# SLT3-PAY-1Q2T_P4.net
KiCad netlist of a schematic drawn in Altium Designer
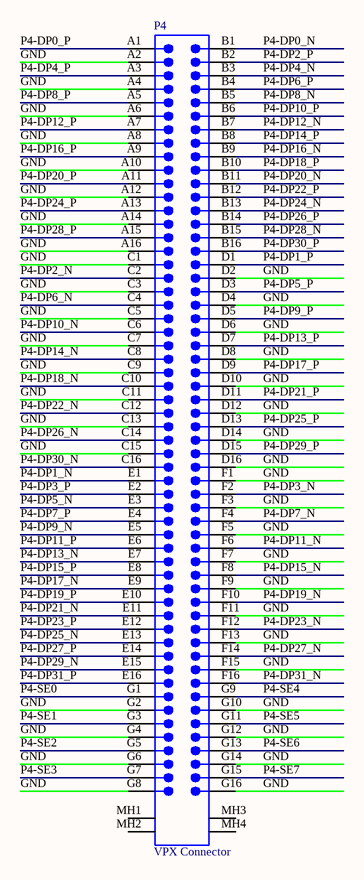
[diagram p0: SLT3-PAY-1Q2T_P4.SchDoc]

(export (version "E")
  (design (tool "Eeschema 10.0.6"))
  (components
    (comp (ref "P4")
      (value "VPX Connector")
      (footprint "BTB1-8-4H112M")
      (description "Ruggedized Board-to-Board Connector, Right Angle, 7-Row, Pitch 1.8mm, 112-Position")
      (fields (field (name "MANUFACTURER") "TE") (field (name "MANUFACTURER PART NUMBER") "2102771-1"))
      (libsource (lib "SVPX") (part "2102771-1"))
    )
  )
  (nets
    (net (code "1") (name "/GND") (class "Default")
      (node (ref "P4") (pin "A10") (pinfunction "A10_A10") (pintype "passive"))
      (node (ref "P4") (pin "A12") (pinfunction "A12_A12") (pintype "passive"))
      (node (ref "P4") (pin "A14") (pinfunction "A14_A14") (pintype "passive"))
      (node (ref "P4") (pin "A16") (pinfunction "A16_A16") (pintype "passive"))
      (node (ref "P4") (pin "A2") (pinfunction "A2_A2") (pintype "passive"))
      (node (ref "P4") (pin "A4") (pinfunction "A4_A4") (pintype "passive"))
      (node (ref "P4") (pin "A6") (pinfunction "A6_A6") (pintype "passive"))
      (node (ref "P4") (pin "A8") (pinfunction "A8_A8") (pintype "passive"))
      (node (ref "P4") (pin "C1") (pinfunction "C1_C1") (pintype "passive"))
      (node (ref "P4") (pin "C11") (pinfunction "C11_C11") (pintype "passive"))
      (node (ref "P4") (pin "C13") (pinfunction "C13_C13") (pintype "passive"))
      (node (ref "P4") (pin "C15") (pinfunction "C15_C15") (pintype "passive"))
      (node (ref "P4") (pin "C3") (pinfunction "C3_C3") (pintype "passive"))
      (node (ref "P4") (pin "C5") (pinfunction "C5_C5") (pintype "passive"))
      (node (ref "P4") (pin "C7") (pinfunction "C7_C7") (pintype "passive"))
      (node (ref "P4") (pin "C9") (pinfunction "C9_C9") (pintype "passive"))
      (node (ref "P4") (pin "D10") (pinfunction "D10_D10") (pintype "passive"))
      (node (ref "P4") (pin "D12") (pinfunction "D12_D12") (pintype "passive"))
      (node (ref "P4") (pin "D14") (pinfunction "D14_D14") (pintype "passive"))
      (node (ref "P4") (pin "D16") (pinfunction "D16_D16") (pintype "passive"))
      (node (ref "P4") (pin "D2") (pinfunction "D2_D2") (pintype "passive"))
      (node (ref "P4") (pin "D4") (pinfunction "D4_D4") (pintype "passive"))
      (node (ref "P4") (pin "D6") (pinfunction "D6_D6") (pintype "passive"))
      (node (ref "P4") (pin "D8") (pinfunction "D8_D8") (pintype "passive"))
      (node (ref "P4") (pin "F1") (pinfunction "F1_F1") (pintype "passive"))
      (node (ref "P4") (pin "F11") (pinfunction "F11_F11") (pintype "passive"))
      (node (ref "P4") (pin "F13") (pinfunction "F13_F13") (pintype "passive"))
      (node (ref "P4") (pin "F15") (pinfunction "F15_F15") (pintype "passive"))
      (node (ref "P4") (pin "F3") (pinfunction "F3_F3") (pintype "passive"))
      (node (ref "P4") (pin "F5") (pinfunction "F5_F5") (pintype "passive"))
      (node (ref "P4") (pin "F7") (pinfunction "F7_F7") (pintype "passive"))
      (node (ref "P4") (pin "F9") (pinfunction "F9_F9") (pintype "passive"))
      (node (ref "P4") (pin "G10") (pinfunction "G10_G10") (pintype "passive"))
      (node (ref "P4") (pin "G12") (pinfunction "G12_G12") (pintype "passive"))
      (node (ref "P4") (pin "G14") (pinfunction "G14_G14") (pintype "passive"))
      (node (ref "P4") (pin "G16") (pinfunction "G16_G16") (pintype "passive"))
      (node (ref "P4") (pin "G2") (pinfunction "G2_G2") (pintype "passive"))
      (node (ref "P4") (pin "G4") (pinfunction "G4_G4") (pintype "passive"))
      (node (ref "P4") (pin "G6") (pinfunction "G6_G6") (pintype "passive"))
      (node (ref "P4") (pin "G8") (pinfunction "G8_G8") (pintype "passive"))
    )
    (net (code "2") (name "/P4-DP0_N") (class "Default")
      (node (ref "P4") (pin "B1") (pinfunction "B1_B1") (pintype "passive"))
    )
    (net (code "3") (name "/P4-DP0_P") (class "Default")
      (node (ref "P4") (pin "A1") (pinfunction "A1_A1") (pintype "passive"))
    )
    (net (code "4") (name "/P4-DP1_N") (class "Default")
      (node (ref "P4") (pin "E1") (pinfunction "E1_E1") (pintype "passive"))
    )
    (net (code "5") (name "/P4-DP1_P") (class "Default")
      (node (ref "P4") (pin "D1") (pinfunction "D1_D1") (pintype "passive"))
    )
    (net (code "6") (name "/P4-DP2_N") (class "Default")
      (node (ref "P4") (pin "C2") (pinfunction "C2_C2") (pintype "passive"))
    )
    (net (code "7") (name "/P4-DP2_P") (class "Default")
      (node (ref "P4") (pin "B2") (pinfunction "B2_B2") (pintype "passive"))
    )
    (net (code "8") (name "/P4-DP3_N") (class "Default")
      (node (ref "P4") (pin "F2") (pinfunction "F2_F2") (pintype "passive"))
    )
    (net (code "9") (name "/P4-DP3_P") (class "Default")
      (node (ref "P4") (pin "E2") (pinfunction "E2_E2") (pintype "passive"))
    )
    (net (code "10") (name "/P4-DP4_N") (class "Default")
      (node (ref "P4") (pin "B3") (pinfunction "B3_B3") (pintype "passive"))
    )
    (net (code "11") (name "/P4-DP4_P") (class "Default")
      (node (ref "P4") (pin "A3") (pinfunction "A3_A3") (pintype "passive"))
    )
    (net (code "12") (name "/P4-DP5_N") (class "Default")
      (node (ref "P4") (pin "E3") (pinfunction "E3_E3") (pintype "passive"))
    )
    (net (code "13") (name "/P4-DP5_P") (class "Default")
      (node (ref "P4") (pin "D3") (pinfunction "D3_D3") (pintype "passive"))
    )
    (net (code "14") (name "/P4-DP6_N") (class "Default")
      (node (ref "P4") (pin "C4") (pinfunction "C4_C4") (pintype "passive"))
    )
    (net (code "15") (name "/P4-DP6_P") (class "Default")
      (node (ref "P4") (pin "B4") (pinfunction "B4_B4") (pintype "passive"))
    )
    (net (code "16") (name "/P4-DP7_N") (class "Default")
      (node (ref "P4") (pin "F4") (pinfunction "F4_F4") (pintype "passive"))
    )
    (net (code "17") (name "/P4-DP7_P") (class "Default")
      (node (ref "P4") (pin "E4") (pinfunction "E4_E4") (pintype "passive"))
    )
    (net (code "18") (name "/P4-DP8_N") (class "Default")
      (node (ref "P4") (pin "B5") (pinfunction "B5_B5") (pintype "passive"))
    )
    (net (code "19") (name "/P4-DP8_P") (class "Default")
      (node (ref "P4") (pin "A5") (pinfunction "A5_A5") (pintype "passive"))
    )
    (net (code "20") (name "/P4-DP9_N") (class "Default")
      (node (ref "P4") (pin "E5") (pinfunction "E5_E5") (pintype "passive"))
    )
    (net (code "21") (name "/P4-DP9_P") (class "Default")
      (node (ref "P4") (pin "D5") (pinfunction "D5_D5") (pintype "passive"))
    )
    (net (code "22") (name "/P4-DP10_N") (class "Default")
      (node (ref "P4") (pin "C6") (pinfunction "C6_C6") (pintype "passive"))
    )
    (net (code "23") (name "/P4-DP10_P") (class "Default")
      (node (ref "P4") (pin "B6") (pinfunction "B6_B6") (pintype "passive"))
    )
    (net (code "24") (name "/P4-DP11_N") (class "Default")
      (node (ref "P4") (pin "F6") (pinfunction "F6_F6") (pintype "passive"))
    )
    (net (code "25") (name "/P4-DP11_P") (class "Default")
      (node (ref "P4") (pin "E6") (pinfunction "E6_E6") (pintype "passive"))
    )
    (net (code "26") (name "/P4-DP12_N") (class "Default")
      (node (ref "P4") (pin "B7") (pinfunction "B7_B7") (pintype "passive"))
    )
    (net (code "27") (name "/P4-DP12_P") (class "Default")
      (node (ref "P4") (pin "A7") (pinfunction "A7_A7") (pintype "passive"))
    )
    (net (code "28") (name "/P4-DP13_N") (class "Default")
      (node (ref "P4") (pin "E7") (pinfunction "E7_E7") (pintype "passive"))
    )
    (net (code "29") (name "/P4-DP13_P") (class "Default")
      (node (ref "P4") (pin "D7") (pinfunction "D7_D7") (pintype "passive"))
    )
    (net (code "30") (name "/P4-DP14_N") (class "Default")
      (node (ref "P4") (pin "C8") (pinfunction "C8_C8") (pintype "passive"))
    )
    (net (code "31") (name "/P4-DP14_P") (class "Default")
      (node (ref "P4") (pin "B8") (pinfunction "B8_B8") (pintype "passive"))
    )
    (net (code "32") (name "/P4-DP15_N") (class "Default")
      (node (ref "P4") (pin "F8") (pinfunction "F8_F8") (pintype "passive"))
    )
    (net (code "33") (name "/P4-DP15_P") (class "Default")
      (node (ref "P4") (pin "E8") (pinfunction "E8_E8") (pintype "passive"))
    )
    (net (code "34") (name "/P4-DP16_N") (class "Default")
      (node (ref "P4") (pin "B9") (pinfunction "B9_B9") (pintype "passive"))
    )
    (net (code "35") (name "/P4-DP16_P") (class "Default")
      (node (ref "P4") (pin "A9") (pinfunction "A9_A9") (pintype "passive"))
    )
    (net (code "36") (name "/P4-DP17_N") (class "Default")
      (node (ref "P4") (pin "E9") (pinfunction "E9_E9") (pintype "passive"))
    )
    (net (code "37") (name "/P4-DP17_P") (class "Default")
      (node (ref "P4") (pin "D9") (pinfunction "D9_D9") (pintype "passive"))
    )
    (net (code "38") (name "/P4-DP18_N") (class "Default")
      (node (ref "P4") (pin "C10") (pinfunction "C10_C10") (pintype "passive"))
    )
    (net (code "39") (name "/P4-DP18_P") (class "Default")
      (node (ref "P4") (pin "B10") (pinfunction "B10_B10") (pintype "passive"))
    )
    (net (code "40") (name "/P4-DP19_N") (class "Default")
      (node (ref "P4") (pin "F10") (pinfunction "F10_F10") (pintype "passive"))
    )
    (net (code "41") (name "/P4-DP19_P") (class "Default")
      (node (ref "P4") (pin "E10") (pinfunction "E10_E10") (pintype "passive"))
    )
    (net (code "42") (name "/P4-DP20_N") (class "Default")
      (node (ref "P4") (pin "B11") (pinfunction "B11_B11") (pintype "passive"))
    )
    (net (code "43") (name "/P4-DP20_P") (class "Default")
      (node (ref "P4") (pin "A11") (pinfunction "A11_A11") (pintype "passive"))
    )
    (net (code "44") (name "/P4-DP21_N") (class "Default")
      (node (ref "P4") (pin "E11") (pinfunction "E11_E11") (pintype "passive"))
    )
    (net (code "45") (name "/P4-DP21_P") (class "Default")
      (node (ref "P4") (pin "D11") (pinfunction "D11_D11") (pintype "passive"))
    )
    (net (code "46") (name "/P4-DP22_N") (class "Default")
      (node (ref "P4") (pin "C12") (pinfunction "C12_C12") (pintype "passive"))
    )
    (net (code "47") (name "/P4-DP22_P") (class "Default")
      (node (ref "P4") (pin "B12") (pinfunction "B12_B12") (pintype "passive"))
    )
    (net (code "48") (name "/P4-DP23_N") (class "Default")
      (node (ref "P4") (pin "F12") (pinfunction "F12_F12") (pintype "passive"))
    )
    (net (code "49") (name "/P4-DP23_P") (class "Default")
      (node (ref "P4") (pin "E12") (pinfunction "E12_E12") (pintype "passive"))
    )
    (net (code "50") (name "/P4-DP24_N") (class "Default")
      (node (ref "P4") (pin "B13") (pinfunction "B13_B13") (pintype "passive"))
    )
    (net (code "51") (name "/P4-DP24_P") (class "Default")
      (node (ref "P4") (pin "A13") (pinfunction "A13_A13") (pintype "passive"))
    )
    (net (code "52") (name "/P4-DP25_N") (class "Default")
      (node (ref "P4") (pin "E13") (pinfunction "E13_E13") (pintype "passive"))
    )
    (net (code "53") (name "/P4-DP25_P") (class "Default")
      (node (ref "P4") (pin "D13") (pinfunction "D13_D13") (pintype "passive"))
    )
    (net (code "54") (name "/P4-DP26_N") (class "Default")
      (node (ref "P4") (pin "C14") (pinfunction "C14_C14") (pintype "passive"))
    )
    (net (code "55") (name "/P4-DP26_P") (class "Default")
      (node (ref "P4") (pin "B14") (pinfunction "B14_B14") (pintype "passive"))
    )
    (net (code "56") (name "/P4-DP27_N") (class "Default")
      (node (ref "P4") (pin "F14") (pinfunction "F14_F14") (pintype "passive"))
    )
    (net (code "57") (name "/P4-DP27_P") (class "Default")
      (node (ref "P4") (pin "E14") (pinfunction "E14_E14") (pintype "passive"))
    )
    (net (code "58") (name "/P4-DP28_N") (class "Default")
      (node (ref "P4") (pin "B15") (pinfunction "B15_B15") (pintype "passive"))
    )
    (net (code "59") (name "/P4-DP28_P") (class "Default")
      (node (ref "P4") (pin "A15") (pinfunction "A15_A15") (pintype "passive"))
    )
    (net (code "60") (name "/P4-DP29_N") (class "Default")
      (node (ref "P4") (pin "E15") (pinfunction "E15_E15") (pintype "passive"))
    )
    (net (code "61") (name "/P4-DP29_P") (class "Default")
      (node (ref "P4") (pin "D15") (pinfunction "D15_D15") (pintype "passive"))
    )
    (net (code "62") (name "/P4-DP30_N") (class "Default")
      (node (ref "P4") (pin "C16") (pinfunction "C16_C16") (pintype "passive"))
    )
    (net (code "63") (name "/P4-DP30_P") (class "Default")
      (node (ref "P4") (pin "B16") (pinfunction "B16_B16") (pintype "passive"))
    )
    (net (code "64") (name "/P4-DP31_N") (class "Default")
      (node (ref "P4") (pin "F16") (pinfunction "F16_F16") (pintype "passive"))
    )
    (net (code "65") (name "/P4-DP31_P") (class "Default")
      (node (ref "P4") (pin "E16") (pinfunction "E16_E16") (pintype "passive"))
    )
    (net (code "66") (name "/P4-SE0") (class "Default")
      (node (ref "P4") (pin "G1") (pinfunction "G1_G1") (pintype "passive"))
    )
    (net (code "67") (name "/P4-SE1") (class "Default")
      (node (ref "P4") (pin "G3") (pinfunction "G3_G3") (pintype "passive"))
    )
    (net (code "68") (name "/P4-SE2") (class "Default")
      (node (ref "P4") (pin "G5") (pinfunction "G5_G5") (pintype "passive"))
    )
    (net (code "69") (name "/P4-SE3") (class "Default")
      (node (ref "P4") (pin "G7") (pinfunction "G7_G7") (pintype "passive"))
    )
    (net (code "70") (name "/P4-SE4") (class "Default")
      (node (ref "P4") (pin "G9") (pinfunction "G9_G9") (pintype "passive"))
    )
    (net (code "71") (name "/P4-SE5") (class "Default")
      (node (ref "P4") (pin "G11") (pinfunction "G11_G11") (pintype "passive"))
    )
    (net (code "72") (name "/P4-SE6") (class "Default")
      (node (ref "P4") (pin "G13") (pinfunction "G13_G13") (pintype "passive"))
    )
    (net (code "73") (name "/P4-SE7") (class "Default")
      (node (ref "P4") (pin "G15") (pinfunction "G15_G15") (pintype "passive"))
    )
    (net (code "74") (name "unconnected-(P4-PadMH1)") (class "Default")
      (node (ref "P4") (pin "MH1") (pinfunction "MH1_MH1") (pintype "passive"))
    )
    (net (code "75") (name "unconnected-(P4-PadMH2)") (class "Default")
      (node (ref "P4") (pin "MH2") (pinfunction "MH2_MH2") (pintype "passive"))
    )
    (net (code "76") (name "unconnected-(P4-PadMH3)") (class "Default")
      (node (ref "P4") (pin "MH3") (pinfunction "MH3_MH3") (pintype "passive"))
    )
    (net (code "77") (name "unconnected-(P4-PadMH4)") (class "Default")
      (node (ref "P4") (pin "MH4") (pinfunction "MH4_MH4") (pintype "passive"))
    )
  )
)
